# rfid.net
KiCad netlist of a schematic drawn in Altium Designer
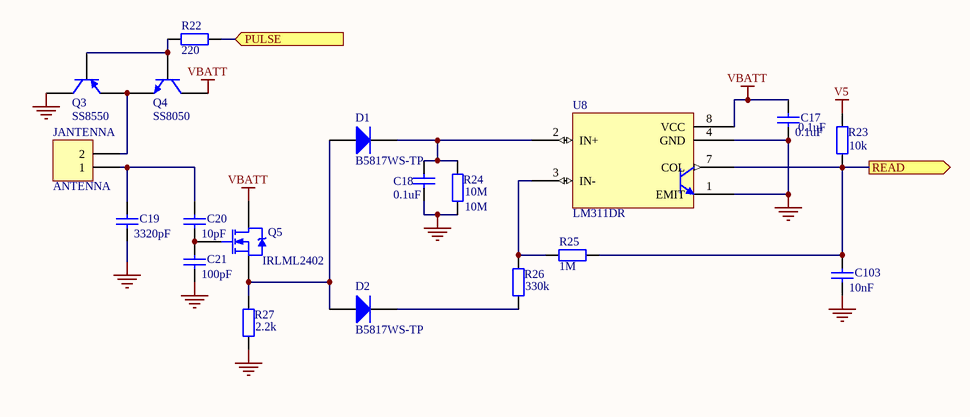
[diagram p0: rfid.SchDoc]

(export (version "E")
  (design (tool "Eeschema 10.0.6"))
  (components
    (comp (ref "C17")
      (value "0.1uF")
      (footprint "CAPC2012L")
      (description "Capacitor")
      (fields (field (name "ALTIUM_VALUE") "0.1uF") (field (name "PUBLISHER") "Altium Limited"))
      (libsource (lib "*") (part "Cap"))
    )
    (comp (ref "C18")
      (value "0.1uF")
      (footprint "CAPC1608L")
      (description "Capacitor")
      (fields (field (name "PUBLISHER") "Altium Limited"))
      (libsource (lib "*") (part "Cap"))
    )
    (comp (ref "C19")
      (value "3320pF")
      (footprint "CAPC1608L")
      (description "Capacitor")
      (fields (field (name "PUBLISHER") "Altium Limited"))
      (libsource (lib "*") (part "Cap"))
    )
    (comp (ref "C20")
      (value "10pF")
      (footprint "CAPC1608L")
      (description "Capacitor")
      (fields (field (name "PUBLISHER") "Altium Limited"))
      (libsource (lib "*") (part "Cap"))
    )
    (comp (ref "C21")
      (value "100pF")
      (footprint "CAPC1608L")
      (description "Capacitor")
      (fields (field (name "PUBLISHER") "Altium Limited"))
      (libsource (lib "*") (part "Cap"))
    )
    (comp (ref "C103")
      (value "10nF")
      (footprint "CAPC1608L")
      (description "Capacitor")
      (fields (field (name "PUBLISHER") "Altium Limited"))
      (libsource (lib "*") (part "Cap"))
    )
    (comp (ref "D1")
      (value "B5817WS-TP")
      (footprint "SOD_323")
      (libsource (lib "components") (part "B5817WS-TP"))
    )
    (comp (ref "D2")
      (value "B5817WS-TP")
      (footprint "SOD_323")
      (libsource (lib "components") (part "B5817WS-TP"))
    )
    (comp (ref "JANTENNA")
      (value "ANTENNA")
      (footprint "HDR1X2")
      (description "Header, 2-Pin")
      (fields (field (name "PUBLISHER") "Altium Limited"))
      (libsource (lib "*") (part "Header 2"))
    )
    (comp (ref "Q3") (value "SS8550") (footprint "SOT23_BJT") (libsource (lib "components") (part "SS8550")))
    (comp (ref "Q4") (value "SS8050") (footprint "SOT23_BJT") (libsource (lib "components") (part "SS8050")))
    (comp (ref "Q5")
      (value "IRLML2402")
      (footprint "SOT-23_N")
      (description "HEXFET Power MOSFET")
      (fields (field (name "PUBLISHER") "Altium Limited"))
      (libsource (lib "IR Discrete MOSFET - Power") (part "IRLML2402"))
    )
    (comp (ref "R22")
      (value "220")
      (footprint "RESC1608L")
      (description "Resistor")
      (fields (field (name "Comment") "2.2k") (field (name "PUBLISHER") "Altium Limited"))
      (libsource (lib "") (part "Res2_1"))
    )
    (comp (ref "R23")
      (value "10k")
      (footprint "RESC1608L")
      (description "Resistor")
      (fields (field (name "PUBLISHER") "Altium Limited"))
      (libsource (lib "") (part "Res2_2"))
    )
    (comp (ref "R24")
      (value "10M")
      (footprint "RESC1608L")
      (description "Resistor")
      (fields (field (name "ALTIUM_VALUE") "10M") (field (name "PUBLISHER") "Altium Limited"))
      (libsource (lib "*") (part "Res2"))
    )
    (comp (ref "R25")
      (value "1M")
      (footprint "RESC1608L")
      (description "Resistor")
      (fields (field (name "PUBLISHER") "Altium Limited"))
      (libsource (lib "") (part "Res2_1"))
    )
    (comp (ref "R26")
      (value "330k")
      (footprint "RESC1608L")
      (description "Resistor")
      (fields (field (name "PUBLISHER") "Altium Limited"))
      (libsource (lib "*") (part "Res2"))
    )
    (comp (ref "R27")
      (value "2.2k")
      (footprint "RESC1608L")
      (description "Resistor")
      (fields (field (name "PUBLISHER") "Altium Limited"))
      (libsource (lib "*") (part "Res2"))
    )
    (comp (ref "U8") (value "LM311DR") (footprint "LM311DR") (libsource (lib "components") (part "LM311DR")))
  )
  (nets
    (net (code "1") (name "/PULSE") (class "Default")
      (node (ref "R22") (pin "2") (pinfunction "2_2") (pintype "passive"))
    )
    (net (code "2") (name "/READ") (class "Default")
      (node (ref "C103") (pin "2") (pinfunction "2_2") (pintype "passive"))
      (node (ref "R23") (pin "2") (pinfunction "2_2") (pintype "passive"))
      (node (ref "R25") (pin "2") (pinfunction "2_2") (pintype "passive"))
      (node (ref "U8") (pin "7") (pinfunction "COL_7") (pintype "output"))
    )
    (net (code "3") (name "GND") (class "Default")
      (node (ref "C103") (pin "1") (pinfunction "1_1") (pintype "passive"))
      (node (ref "C17") (pin "2") (pinfunction "2_2") (pintype "passive"))
      (node (ref "C18") (pin "1") (pinfunction "1_1") (pintype "passive"))
      (node (ref "C19") (pin "1") (pinfunction "1_1") (pintype "passive"))
      (node (ref "C21") (pin "1") (pinfunction "1_1") (pintype "passive"))
      (node (ref "Q3") (pin "C") (pinfunction "C_C") (pintype "passive"))
      (node (ref "R24") (pin "2") (pinfunction "2_2") (pintype "passive"))
      (node (ref "R27") (pin "2") (pinfunction "2_2") (pintype "passive"))
      (node (ref "U8") (pin "1") (pinfunction "EMIT_1") (pintype "power_in"))
      (node (ref "U8") (pin "4") (pinfunction "GND_4") (pintype "power_in"))
    )
    (net (code "4") (name "Net-(C19-Pad2)") (class "Default")
      (node (ref "C19") (pin "2") (pinfunction "2_2") (pintype "passive"))
      (node (ref "C20") (pin "2") (pinfunction "2_2") (pintype "passive"))
      (node (ref "JANTENNA") (pin "1") (pinfunction "1_1") (pintype "passive"))
    )
    (net (code "5") (name "Net-(D2-Pad2)") (class "Default")
      (node (ref "D2") (pin "2") (pinfunction "2_2") (pintype "passive"))
      (node (ref "R26") (pin "2") (pinfunction "2_2") (pintype "passive"))
    )
    (net (code "6") (name "Net-(JANTENNA-Pad2)") (class "Default")
      (node (ref "JANTENNA") (pin "2") (pinfunction "2_2") (pintype "passive"))
      (node (ref "Q3") (pin "E") (pinfunction "E_E") (pintype "passive"))
      (node (ref "Q4") (pin "E") (pinfunction "E_E") (pintype "passive"))
    )
    (net (code "7") (name "Net-(Q3-PadB)") (class "Default")
      (node (ref "Q3") (pin "B") (pinfunction "B_B") (pintype "passive"))
      (node (ref "Q4") (pin "B") (pinfunction "B_B") (pintype "passive"))
      (node (ref "R22") (pin "1") (pinfunction "1_1") (pintype "passive"))
    )
    (net (code "8") (name "Net-(Q5-G)") (class "Default")
      (node (ref "C20") (pin "1") (pinfunction "1_1") (pintype "passive"))
      (node (ref "C21") (pin "2") (pinfunction "2_2") (pintype "passive"))
      (node (ref "Q5") (pin "1") (pinfunction "G_1") (pintype "passive"))
    )
    (net (code "9") (name "Net-(Q5-S)") (class "Default")
      (node (ref "D1") (pin "1") (pinfunction "1_1") (pintype "passive"))
      (node (ref "D2") (pin "1") (pinfunction "1_1") (pintype "passive"))
      (node (ref "Q5") (pin "2") (pinfunction "S_2") (pintype "passive"))
      (node (ref "R27") (pin "1") (pinfunction "1_1") (pintype "passive"))
    )
    (net (code "10") (name "Net-(U8-IN+)") (class "Default")
      (node (ref "C18") (pin "2") (pinfunction "2_2") (pintype "passive"))
      (node (ref "D1") (pin "2") (pinfunction "2_2") (pintype "passive"))
      (node (ref "R24") (pin "1") (pinfunction "1_1") (pintype "passive"))
      (node (ref "U8") (pin "2") (pinfunction "IN+_2") (pintype "bidirectional"))
    )
    (net (code "11") (name "Net-(U8-IN-)") (class "Default")
      (node (ref "R25") (pin "1") (pinfunction "1_1") (pintype "passive"))
      (node (ref "R26") (pin "1") (pinfunction "1_1") (pintype "passive"))
      (node (ref "U8") (pin "3") (pinfunction "IN-_3") (pintype "bidirectional"))
    )
    (net (code "12") (name "V5") (class "Default")
      (node (ref "R23") (pin "1") (pinfunction "1_1") (pintype "passive"))
    )
    (net (code "13") (name "VBATT") (class "Default")
      (node (ref "C17") (pin "1") (pinfunction "1_1") (pintype "passive"))
      (node (ref "Q4") (pin "C") (pinfunction "C_C") (pintype "passive"))
      (node (ref "Q5") (pin "3") (pinfunction "D_3") (pintype "passive"))
      (node (ref "U8") (pin "8") (pinfunction "VCC_8") (pintype "power_in"))
    )
  )
)
